# hcgs-cow-baby.net
KiCad netlist of a schematic drawn in EAGLE
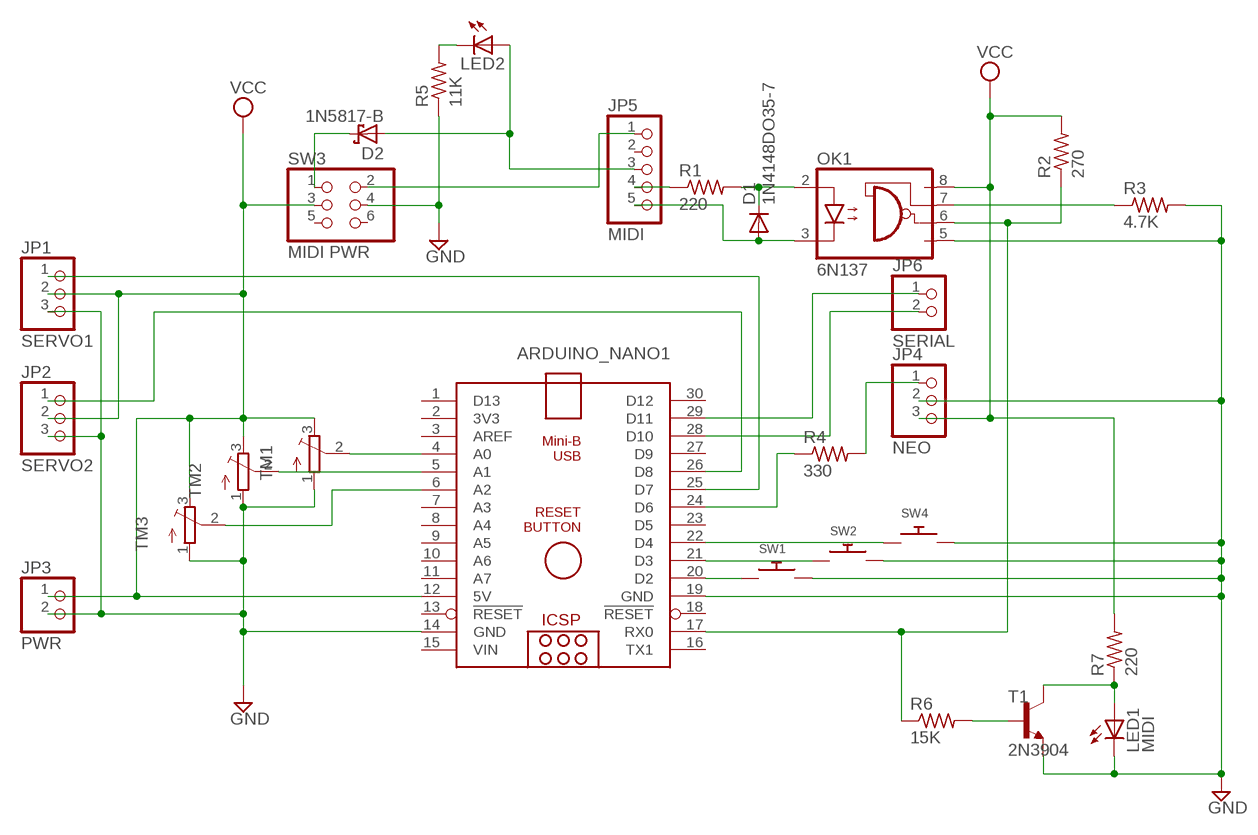
[diagram p0: schematic, sheet 1]

(export (version "E")
  (design (tool "Eeschema 10.0.6"))
  (components
    (comp (ref "ARDUINO_NANO1")
      (value "ARDUINO_NANO_HCARDUINO_NANO_NO_HOLE")
      (footprint "eagle-import:ARDUINO_NANO_NO_HOLE")
      (libsource (lib "eagle-import") (part "ARDUINO_NANO_HCARDUINO_NANO_NO_HOLE"))
    )
    (comp (ref "D1")
      (value "1N4148DO35-7")
      (footprint "eagle-import:DO35-7")
      (libsource (lib "eagle-import") (part "1N4148DO35-7"))
    )
    (comp (ref "D2")
      (value "1N5817-B")
      (footprint "eagle-import:DO41-7.6")
      (libsource (lib "eagle-import") (part "1N5817-B"))
    )
    (comp (ref "JP1")
      (value "SERVO1")
      (footprint "eagle-import:1X03")
      (libsource (lib "eagle-import") (part "PINHD-1X3"))
    )
    (comp (ref "JP2")
      (value "SERVO2")
      (footprint "eagle-import:1X03")
      (libsource (lib "eagle-import") (part "PINHD-1X3"))
    )
    (comp (ref "JP3")
      (value "PWR")
      (footprint "eagle-import:1X02")
      (libsource (lib "eagle-import") (part "PINHD-1X2"))
    )
    (comp (ref "JP4")
      (value "NEO")
      (footprint "eagle-import:1X03")
      (libsource (lib "eagle-import") (part "PINHD-1X3"))
    )
    (comp (ref "JP5")
      (value "MIDI")
      (footprint "eagle-import:1X05")
      (libsource (lib "eagle-import") (part "PINHD-1X5"))
    )
    (comp (ref "JP6")
      (value "SERIAL")
      (footprint "eagle-import:1X02")
      (libsource (lib "eagle-import") (part "PINHD-1X2"))
    )
    (comp (ref "LED1")
      (value "MIDI")
      (footprint "eagle-import:LED5MM")
      (libsource (lib "eagle-import") (part "LED5MM"))
    )
    (comp (ref "LED2")
      (value "LED5MM")
      (footprint "eagle-import:LED5MM")
      (libsource (lib "eagle-import") (part "LED5MM"))
    )
    (comp (ref "OK1")
      (value "6N137")
      (footprint "eagle-import:DIL08")
      (libsource (lib "eagle-import") (part "6N137"))
    )
    (comp (ref "R1")
      (value "220")
      (footprint "eagle-import:0309_12")
      (libsource (lib "eagle-import") (part "R-US_0309/12"))
    )
    (comp (ref "R2")
      (value "270")
      (footprint "eagle-import:0309_12")
      (libsource (lib "eagle-import") (part "R-US_0309/12"))
    )
    (comp (ref "R3")
      (value "4.7K")
      (footprint "eagle-import:0309_12")
      (libsource (lib "eagle-import") (part "R-US_0309/12"))
    )
    (comp (ref "R4")
      (value "330")
      (footprint "eagle-import:0309_12")
      (libsource (lib "eagle-import") (part "R-US_0309/12"))
    )
    (comp (ref "R5")
      (value "11K")
      (footprint "eagle-import:0309_12")
      (libsource (lib "eagle-import") (part "R-US_0309/12"))
    )
    (comp (ref "R6")
      (value "15K")
      (footprint "eagle-import:0309_12")
      (libsource (lib "eagle-import") (part "R-US_0309/12"))
    )
    (comp (ref "R7")
      (value "220")
      (footprint "eagle-import:0309_12")
      (libsource (lib "eagle-import") (part "R-US_0309/12"))
    )
    (comp (ref "SW1")
      (value "SWITCH_PUSHBUTTONEVQ-PE")
      (footprint "eagle-import:TACT_PANA-EVQ")
      (libsource (lib "eagle-import") (part "SWITCH_PUSHBUTTONEVQ-PE"))
    )
    (comp (ref "SW2")
      (value "SWITCH_PUSHBUTTONEVQ-PE")
      (footprint "eagle-import:TACT_PANA-EVQ")
      (libsource (lib "eagle-import") (part "SWITCH_PUSHBUTTONEVQ-PE"))
    )
    (comp (ref "SW3")
      (value "MIDI PWR")
      (footprint "eagle-import:2X03")
      (libsource (lib "eagle-import") (part "PINHD-2X3"))
    )
    (comp (ref "SW4")
      (value "SWITCH_PUSHBUTTONEVQ-PE")
      (footprint "eagle-import:TACT_PANA-EVQ")
      (libsource (lib "eagle-import") (part "SWITCH_PUSHBUTTONEVQ-PE"))
    )
    (comp (ref "T1")
      (value "2N3904")
      (footprint "eagle-import:TO92")
      (libsource (lib "eagle-import") (part "2N3904"))
    )
    (comp (ref "TM1")
      (value "TRIMPOT3386")
      (footprint "eagle-import:TRIM-3386")
      (libsource (lib "eagle-import") (part "TRIMPOT3386"))
    )
    (comp (ref "TM2")
      (value "TRIMPOT3386")
      (footprint "eagle-import:TRIM-3386")
      (libsource (lib "eagle-import") (part "TRIMPOT3386"))
    )
    (comp (ref "TM3")
      (value "TRIMPOT3386")
      (footprint "eagle-import:TRIM-3386")
      (libsource (lib "eagle-import") (part "TRIMPOT3386"))
    )
  )
  (nets
    (net (code "1") (name "/VIN") (class "Default")
      (node (ref "ARDUINO_NANO1") (pin "15") (pinfunction "VIN_15") (pintype "power_in"))
    )
    (net (code "2") (name "GND") (class "Default")
      (node (ref "ARDUINO_NANO1") (pin "14") (pinfunction "GND_14") (pintype "power_in"))
      (node (ref "ARDUINO_NANO1") (pin "19") (pinfunction "GND_19") (pintype "power_in"))
      (node (ref "JP1") (pin "3") (pinfunction "3_3") (pintype "passive"))
      (node (ref "JP2") (pin "3") (pinfunction "3_3") (pintype "passive"))
      (node (ref "JP3") (pin "2") (pinfunction "2_2") (pintype "passive"))
      (node (ref "JP4") (pin "2") (pinfunction "2_2") (pintype "passive"))
      (node (ref "LED1") (pin "K") (pinfunction "C_K") (pintype "passive"))
      (node (ref "OK1") (pin "5") (pinfunction "GND_5") (pintype "passive"))
      (node (ref "R3") (pin "2") (pinfunction "2_2") (pintype "passive"))
      (node (ref "R5") (pin "1") (pinfunction "1_1") (pintype "passive"))
      (node (ref "SW1") (pin "P$2") (pinfunction "P$2_P$2") (pintype "passive"))
      (node (ref "SW2") (pin "P$2") (pinfunction "P$2_P$2") (pintype "passive"))
      (node (ref "SW3") (pin "4") (pinfunction "4_4") (pintype "passive"))
      (node (ref "SW4") (pin "P$2") (pinfunction "P$2_P$2") (pintype "passive"))
      (node (ref "T1") (pin "3") (pinfunction "E_3") (pintype "passive"))
      (node (ref "TM1") (pin "1") (pinfunction "A_1") (pintype "passive"))
      (node (ref "TM2") (pin "1") (pinfunction "A_1") (pintype "passive"))
      (node (ref "TM3") (pin "1") (pinfunction "A_1") (pintype "passive"))
    )
    (net (code "3") (name "Net-(ARDUINO_NANO1-A0)") (class "Default")
      (node (ref "ARDUINO_NANO1") (pin "4") (pinfunction "A0_4") (pintype "bidirectional"))
      (node (ref "TM1") (pin "2") (pinfunction "S_2") (pintype "passive"))
    )
    (net (code "4") (name "Net-(ARDUINO_NANO1-A1)") (class "Default")
      (node (ref "ARDUINO_NANO1") (pin "5") (pinfunction "A1_5") (pintype "bidirectional"))
      (node (ref "TM2") (pin "2") (pinfunction "S_2") (pintype "passive"))
    )
    (net (code "5") (name "Net-(ARDUINO_NANO1-A2)") (class "Default")
      (node (ref "ARDUINO_NANO1") (pin "6") (pinfunction "A2_6") (pintype "bidirectional"))
      (node (ref "TM3") (pin "2") (pinfunction "S_2") (pintype "passive"))
    )
    (net (code "6") (name "Net-(ARDUINO_NANO1-D2)") (class "Default")
      (node (ref "ARDUINO_NANO1") (pin "20") (pinfunction "D2_20") (pintype "bidirectional"))
      (node (ref "SW1") (pin "P$1") (pinfunction "P$1_P$1") (pintype "passive"))
    )
    (net (code "7") (name "Net-(ARDUINO_NANO1-D3)") (class "Default")
      (node (ref "ARDUINO_NANO1") (pin "21") (pinfunction "D3_21") (pintype "bidirectional"))
      (node (ref "SW2") (pin "P$1") (pinfunction "P$1_P$1") (pintype "passive"))
    )
    (net (code "8") (name "Net-(ARDUINO_NANO1-D4)") (class "Default")
      (node (ref "ARDUINO_NANO1") (pin "22") (pinfunction "D4_22") (pintype "bidirectional"))
      (node (ref "SW4") (pin "P$1") (pinfunction "P$1_P$1") (pintype "passive"))
    )
    (net (code "9") (name "Net-(ARDUINO_NANO1-D6)") (class "Default")
      (node (ref "ARDUINO_NANO1") (pin "24") (pinfunction "D6_24") (pintype "bidirectional"))
      (node (ref "R4") (pin "1") (pinfunction "1_1") (pintype "passive"))
    )
    (net (code "10") (name "Net-(ARDUINO_NANO1-D7)") (class "Default")
      (node (ref "ARDUINO_NANO1") (pin "25") (pinfunction "D7_25") (pintype "bidirectional"))
      (node (ref "JP1") (pin "1") (pinfunction "1_1") (pintype "passive"))
    )
    (net (code "11") (name "Net-(ARDUINO_NANO1-D8)") (class "Default")
      (node (ref "ARDUINO_NANO1") (pin "26") (pinfunction "D8_26") (pintype "bidirectional"))
      (node (ref "JP2") (pin "1") (pinfunction "1_1") (pintype "passive"))
    )
    (net (code "12") (name "Net-(ARDUINO_NANO1-D10)") (class "Default")
      (node (ref "ARDUINO_NANO1") (pin "28") (pinfunction "D10_28") (pintype "bidirectional"))
      (node (ref "JP6") (pin "2") (pinfunction "2_2") (pintype "passive"))
    )
    (net (code "13") (name "Net-(ARDUINO_NANO1-D11)") (class "Default")
      (node (ref "ARDUINO_NANO1") (pin "29") (pinfunction "D11_29") (pintype "bidirectional"))
      (node (ref "JP6") (pin "1") (pinfunction "1_1") (pintype "passive"))
    )
    (net (code "14") (name "Net-(ARDUINO_NANO1-RX0)") (class "Default")
      (node (ref "ARDUINO_NANO1") (pin "17") (pinfunction "RX0_17") (pintype "bidirectional"))
      (node (ref "OK1") (pin "6") (pinfunction "VO_6") (pintype "passive"))
      (node (ref "R2") (pin "1") (pinfunction "1_1") (pintype "passive"))
      (node (ref "R6") (pin "1") (pinfunction "1_1") (pintype "passive"))
    )
    (net (code "15") (name "Net-(D2-PadA)") (class "Default")
      (node (ref "D2") (pin "A") (pinfunction "A_A") (pintype "passive"))
      (node (ref "JP5") (pin "3") (pinfunction "3_3") (pintype "passive"))
      (node (ref "LED2") (pin "A") (pinfunction "A_A") (pintype "passive"))
    )
    (net (code "16") (name "Net-(D2-PadC)") (class "Default")
      (node (ref "D2") (pin "C") (pinfunction "C_C") (pintype "passive"))
      (node (ref "SW3") (pin "1") (pinfunction "1_1") (pintype "passive"))
    )
    (net (code "17") (name "Net-(JP4-Pad1)") (class "Default")
      (node (ref "JP4") (pin "1") (pinfunction "1_1") (pintype "passive"))
      (node (ref "R4") (pin "2") (pinfunction "2_2") (pintype "passive"))
    )
    (net (code "18") (name "Net-(JP5-Pad1)") (class "Default")
      (node (ref "JP5") (pin "1") (pinfunction "1_1") (pintype "passive"))
      (node (ref "SW3") (pin "2") (pinfunction "2_2") (pintype "passive"))
    )
    (net (code "19") (name "Net-(JP5-Pad4)") (class "Default")
      (node (ref "JP5") (pin "4") (pinfunction "4_4") (pintype "passive"))
      (node (ref "R1") (pin "1") (pinfunction "1_1") (pintype "passive"))
    )
    (net (code "20") (name "Net-(LED2-C)") (class "Default")
      (node (ref "LED2") (pin "K") (pinfunction "C_K") (pintype "passive"))
      (node (ref "R5") (pin "2") (pinfunction "2_2") (pintype "passive"))
    )
    (net (code "21") (name "Net-(OK1-A)") (class "Default")
      (node (ref "D1") (pin "C") (pinfunction "C_C") (pintype "passive"))
      (node (ref "OK1") (pin "2") (pinfunction "A_2") (pintype "passive"))
      (node (ref "R1") (pin "2") (pinfunction "2_2") (pintype "passive"))
    )
    (net (code "22") (name "Net-(OK1-C)") (class "Default")
      (node (ref "D1") (pin "A") (pinfunction "A_A") (pintype "passive"))
      (node (ref "JP5") (pin "5") (pinfunction "5_5") (pintype "passive"))
      (node (ref "OK1") (pin "3") (pinfunction "C_3") (pintype "passive"))
    )
    (net (code "23") (name "Net-(OK1-VE)") (class "Default")
      (node (ref "OK1") (pin "7") (pinfunction "VE_7") (pintype "passive"))
      (node (ref "R3") (pin "1") (pinfunction "1_1") (pintype "passive"))
    )
    (net (code "24") (name "Net-(T1-B)") (class "Default")
      (node (ref "R6") (pin "2") (pinfunction "2_2") (pintype "passive"))
      (node (ref "T1") (pin "2") (pinfunction "B_2") (pintype "passive"))
    )
    (net (code "25") (name "Net-(T1-C)") (class "Default")
      (node (ref "LED1") (pin "A") (pinfunction "A_A") (pintype "passive"))
      (node (ref "R7") (pin "1") (pinfunction "1_1") (pintype "passive"))
      (node (ref "T1") (pin "1") (pinfunction "C_1") (pintype "passive"))
    )
    (net (code "26") (name "VCC") (class "Default")
      (node (ref "ARDUINO_NANO1") (pin "12") (pinfunction "5V_12") (pintype "power_in"))
      (node (ref "JP1") (pin "2") (pinfunction "2_2") (pintype "passive"))
      (node (ref "JP2") (pin "2") (pinfunction "2_2") (pintype "passive"))
      (node (ref "JP3") (pin "1") (pinfunction "1_1") (pintype "passive"))
      (node (ref "JP4") (pin "3") (pinfunction "3_3") (pintype "passive"))
      (node (ref "OK1") (pin "8") (pinfunction "VCC_8") (pintype "passive"))
      (node (ref "R2") (pin "2") (pinfunction "2_2") (pintype "passive"))
      (node (ref "R7") (pin "2") (pinfunction "2_2") (pintype "passive"))
      (node (ref "SW3") (pin "3") (pinfunction "3_3") (pintype "passive"))
      (node (ref "TM1") (pin "3") (pinfunction "E_3") (pintype "passive"))
      (node (ref "TM2") (pin "3") (pinfunction "E_3") (pintype "passive"))
      (node (ref "TM3") (pin "3") (pinfunction "E_3") (pintype "passive"))
    )
    (net (code "27") (name "unconnected-(ARDUINO_NANO1-3V3-Pad2)") (class "Default")
      (node (ref "ARDUINO_NANO1") (pin "2") (pinfunction "3V3_2") (pintype "output"))
    )
    (net (code "28") (name "unconnected-(ARDUINO_NANO1-A3-Pad7)") (class "Default")
      (node (ref "ARDUINO_NANO1") (pin "7") (pinfunction "A3_7") (pintype "bidirectional"))
    )
    (net (code "29") (name "unconnected-(ARDUINO_NANO1-A4-Pad8)") (class "Default")
      (node (ref "ARDUINO_NANO1") (pin "8") (pinfunction "A4_8") (pintype "bidirectional"))
    )
    (net (code "30") (name "unconnected-(ARDUINO_NANO1-A5-Pad9)") (class "Default")
      (node (ref "ARDUINO_NANO1") (pin "9") (pinfunction "A5_9") (pintype "bidirectional"))
    )
    (net (code "31") (name "unconnected-(ARDUINO_NANO1-A6-Pad10)") (class "Default")
      (node (ref "ARDUINO_NANO1") (pin "10") (pinfunction "A6_10") (pintype "bidirectional"))
    )
    (net (code "32") (name "unconnected-(ARDUINO_NANO1-A7-Pad11)") (class "Default")
      (node (ref "ARDUINO_NANO1") (pin "11") (pinfunction "A7_11") (pintype "bidirectional"))
    )
    (net (code "33") (name "unconnected-(ARDUINO_NANO1-AREF-Pad3)") (class "Default")
      (node (ref "ARDUINO_NANO1") (pin "3") (pinfunction "AREF_3") (pintype "input"))
    )
    (net (code "34") (name "unconnected-(ARDUINO_NANO1-D5-Pad23)") (class "Default")
      (node (ref "ARDUINO_NANO1") (pin "23") (pinfunction "D5_23") (pintype "bidirectional"))
    )
    (net (code "35") (name "unconnected-(ARDUINO_NANO1-D9-Pad27)") (class "Default")
      (node (ref "ARDUINO_NANO1") (pin "27") (pinfunction "D9_27") (pintype "bidirectional"))
    )
    (net (code "36") (name "unconnected-(ARDUINO_NANO1-D12-Pad30)") (class "Default")
      (node (ref "ARDUINO_NANO1") (pin "30") (pinfunction "D12_30") (pintype "bidirectional"))
    )
    (net (code "37") (name "unconnected-(ARDUINO_NANO1-D13-Pad1)") (class "Default")
      (node (ref "ARDUINO_NANO1") (pin "1") (pinfunction "D13_1") (pintype "bidirectional"))
    )
    (net (code "38") (name "unconnected-(ARDUINO_NANO1-TX1-Pad16)") (class "Default")
      (node (ref "ARDUINO_NANO1") (pin "16") (pinfunction "TX1_16") (pintype "bidirectional"))
    )
    (net (code "39") (name "unconnected-(ARDUINO_NANO1-~{RESET}-Pad13)") (class "Default")
      (node (ref "ARDUINO_NANO1") (pin "13") (pinfunction "~{RESET}_13") (pintype "input"))
    )
    (net (code "40") (name "unconnected-(ARDUINO_NANO1-~{RESET}-Pad18)") (class "Default")
      (node (ref "ARDUINO_NANO1") (pin "18") (pinfunction "~{RESET}_18") (pintype "input"))
    )
    (net (code "41") (name "unconnected-(JP5-Pad2)") (class "Default")
      (node (ref "JP5") (pin "2") (pinfunction "2_2") (pintype "passive"))
    )
    (net (code "42") (name "unconnected-(SW3-Pad5)") (class "Default")
      (node (ref "SW3") (pin "5") (pinfunction "5_5") (pintype "passive"))
    )
    (net (code "43") (name "unconnected-(SW3-Pad6)") (class "Default")
      (node (ref "SW3") (pin "6") (pinfunction "6_6") (pintype "passive"))
    )
  )
)
